# motordriver.net
KiCad netlist of a schematic drawn in Altium Designer
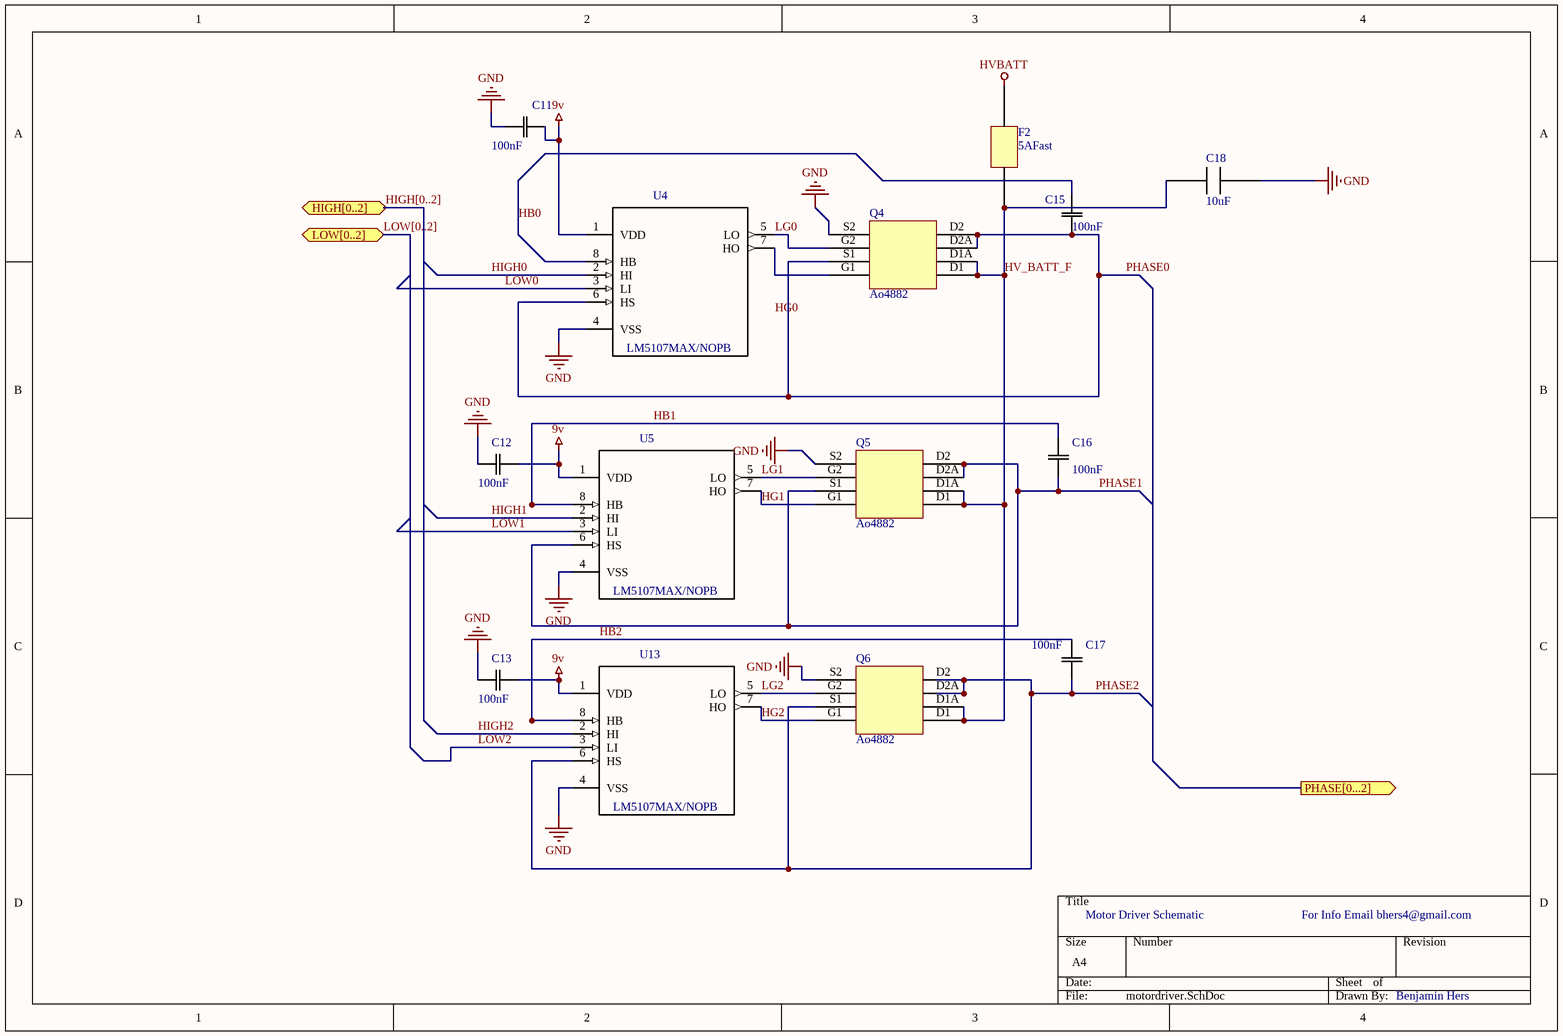
[diagram p0: motordriver.SchDoc]

(export (version "E")
  (design (tool "Eeschema 10.0.6"))
  (components
    (comp (ref "C11")
      (value "100nF")
      (footprint "CAPC2013X110N")
      (description "Capacitor; Ceramic; Cap; .100UF ; Tol+-10%; SMD; Vol-Rtg 50V; X7R, Tape/Reel")
      (fields (field (name "MP") "C0805C104K5RACTU") (field (name "MF") "Kemet"))
      (libsource (lib "100nF-C0805C104K5RACTU") (part "C0805C104K5RACTU"))
    )
    (comp (ref "C12")
      (value "100nF")
      (footprint "CAPC2013X110N")
      (description "Capacitor; Ceramic; Cap; .100UF ; Tol+-10%; SMD; Vol-Rtg 50V; X7R, Tape/Reel")
      (fields (field (name "MP") "C0805C104K5RACTU") (field (name "MF") "Kemet"))
      (libsource (lib "100nF-C0805C104K5RACTU") (part "C0805C104K5RACTU"))
    )
    (comp (ref "C13")
      (value "100nF")
      (footprint "CAPC2013X110N")
      (description "Capacitor; Ceramic; Cap; .100UF ; Tol+-10%; SMD; Vol-Rtg 50V; X7R, Tape/Reel")
      (fields (field (name "MP") "C0805C104K5RACTU") (field (name "MF") "Kemet"))
      (libsource (lib "100nF-C0805C104K5RACTU") (part "C0805C104K5RACTU"))
    )
    (comp (ref "C15")
      (value "100nF")
      (footprint "CAPC2013X110N")
      (description "Capacitor; Ceramic; Cap; .100UF ; Tol+-10%; SMD; Vol-Rtg 50V; X7R, Tape/Reel")
      (fields (field (name "MP") "C0805C104K5RACTU") (field (name "MF") "Kemet"))
      (libsource (lib "") (part "C0805C104K5RACTU_2"))
    )
    (comp (ref "C16")
      (value "100nF")
      (footprint "CAPC2013X110N")
      (description "Capacitor; Ceramic; Cap; .100UF ; Tol+-10%; SMD; Vol-Rtg 50V; X7R, Tape/Reel")
      (fields (field (name "MP") "C0805C104K5RACTU") (field (name "MF") "Kemet"))
      (libsource (lib "") (part "C0805C104K5RACTU_1"))
    )
    (comp (ref "C17")
      (value "100nF")
      (footprint "CAPC2013X110N")
      (description "Capacitor; Ceramic; Cap; .100UF ; Tol+-10%; SMD; Vol-Rtg 50V; X7R, Tape/Reel")
      (fields (field (name "MP") "C0805C104K5RACTU") (field (name "MF") "Kemet"))
      (libsource (lib "") (part "C0805C104K5RACTU_1"))
    )
    (comp (ref "C18")
      (value "10uF")
      (footprint "10uFCAPC3216X100N:CAPC3216X100N")
      (libsource (lib "altium-import") (part "root_0_Component_1_"))
    )
    (comp (ref "F2")
      (value "5AFast")
      (footprint "Fuse1206:1206")
      (libsource (lib "Fuse1206") (part "5AFast1206"))
    )
    (comp (ref "Q4")
      (value "Ao4882")
      (footprint "Ao4882:SOIC127P490X600X175-8N")
      (libsource (lib "Ao4882") (part "Ao4882"))
    )
    (comp (ref "Q5")
      (value "Ao4882")
      (footprint "Ao4882:SOIC127P490X600X175-8N")
      (libsource (lib "Ao4882") (part "Ao4882"))
    )
    (comp (ref "Q6")
      (value "Ao4882")
      (footprint "Ao4882:SOIC127P490X600X175-8N")
      (libsource (lib "Ao4882") (part "Ao4882"))
    )
    (comp (ref "U4")
      (value "LM5107MAX/NOPB")
      (footprint "LM5107MAX_NOPB:SOIC127P620X175-8N")
      (description "MOSFET DRVR 1.4A 2-OUT Hi/Lo Side Full Brdg/Half Brdg Non-Inv 8-Pin SOIC N T/R")
      (fields
        (field (name "DIGI-KEY_PART_NUMBER") "LM5107MAX/NOPBCT-ND")
        (field (name "MF") "Texas Instruments")
      )
      (libsource (lib "LM5107MAX_NOPB") (part "LM5107MAX/NOPB"))
    )
    (comp (ref "U5")
      (value "LM5107MAX/NOPB")
      (footprint "LM5107MAX_NOPB:SOIC127P620X175-8N")
      (description "MOSFET DRVR 1.4A 2-OUT Hi/Lo Side Full Brdg/Half Brdg Non-Inv 8-Pin SOIC N T/R")
      (fields
        (field (name "DIGI-KEY_PART_NUMBER") "LM5107MAX/NOPBCT-ND")
        (field (name "MF") "Texas Instruments")
      )
      (libsource (lib "LM5107MAX_NOPB") (part "LM5107MAX/NOPB"))
    )
    (comp (ref "U13")
      (value "LM5107MAX/NOPB")
      (footprint "LM5107MAX_NOPB:SOIC127P620X175-8N")
      (description "MOSFET DRVR 1.4A 2-OUT Hi/Lo Side Full Brdg/Half Brdg Non-Inv 8-Pin SOIC N T/R")
      (fields
        (field (name "DIGI-KEY_PART_NUMBER") "LM5107MAX/NOPBCT-ND")
        (field (name "MF") "Texas Instruments")
      )
      (libsource (lib "LM5107MAX_NOPB") (part "LM5107MAX/NOPB"))
    )
  )
  (nets
    (net (code "1") (name "/HB0") (class "Default")
      (node (ref "C15") (pin "2") (pinfunction "C2_2") (pintype "passive"))
      (node (ref "U4") (pin "8") (pinfunction "HB_8") (pintype "input"))
    )
    (net (code "2") (name "/HB1") (class "Default")
      (node (ref "C16") (pin "1") (pinfunction "C1_1") (pintype "passive"))
      (node (ref "U5") (pin "8") (pinfunction "HB_8") (pintype "input"))
    )
    (net (code "3") (name "/HB2") (class "Default")
      (node (ref "C17") (pin "1") (pinfunction "C1_1") (pintype "passive"))
      (node (ref "U13") (pin "8") (pinfunction "HB_8") (pintype "input"))
    )
    (net (code "5") (name "/HG1") (class "Default")
      (node (ref "Q5") (pin "G1") (pinfunction "4_G1") (pintype "passive"))
      (node (ref "U5") (pin "7") (pinfunction "HO_7") (pintype "output"))
    )
    (net (code "6") (name "/HG2") (class "Default")
      (node (ref "Q6") (pin "G1") (pinfunction "4_G1") (pintype "passive"))
      (node (ref "U13") (pin "7") (pinfunction "HO_7") (pintype "output"))
    )
    (net (code "7") (name "/HIGH0") (class "Default")
      (node (ref "U4") (pin "2") (pinfunction "HI_2") (pintype "input"))
    )
    (net (code "8") (name "/HIGH1") (class "Default")
      (node (ref "U5") (pin "2") (pinfunction "HI_2") (pintype "input"))
    )
    (net (code "9") (name "/HIGH2") (class "Default")
      (node (ref "U13") (pin "2") (pinfunction "HI_2") (pintype "input"))
    )
    (net (code "11") (name "/HV_BATT_F") (class "Default")
      (node (ref "F2") (pin "Fusein") (pinfunction "In_Fusein") (pintype "passive"))
      (node (ref "Q4") (pin "D1") (pinfunction "5_D1") (pintype "passive"))
      (node (ref "Q4") (pin "D1A") (pinfunction "6_D1A") (pintype "passive"))
      (node (ref "Q5") (pin "D1") (pinfunction "5_D1") (pintype "passive"))
      (node (ref "Q5") (pin "D1A") (pinfunction "6_D1A") (pintype "passive"))
      (node (ref "Q6") (pin "D1") (pinfunction "5_D1") (pintype "passive"))
      (node (ref "Q6") (pin "D1A") (pinfunction "6_D1A") (pintype "passive"))
    )
    (net (code "12") (name "/LG0") (class "Default")
      (node (ref "Q4") (pin "G2") (pinfunction "2_G2") (pintype "passive"))
      (node (ref "U4") (pin "5") (pinfunction "LO_5") (pintype "output"))
    )
    (net (code "13") (name "/LG1") (class "Default")
      (node (ref "Q5") (pin "G2") (pinfunction "2_G2") (pintype "passive"))
      (node (ref "U5") (pin "5") (pinfunction "LO_5") (pintype "output"))
    )
    (net (code "14") (name "/LG2") (class "Default")
      (node (ref "Q6") (pin "G2") (pinfunction "2_G2") (pintype "passive"))
      (node (ref "U13") (pin "5") (pinfunction "LO_5") (pintype "output"))
    )
    (net (code "15") (name "/LOW0") (class "Default")
      (node (ref "U4") (pin "3") (pinfunction "LI_3") (pintype "input"))
    )
    (net (code "16") (name "/LOW1") (class "Default")
      (node (ref "U5") (pin "3") (pinfunction "LI_3") (pintype "input"))
    )
    (net (code "17") (name "/LOW2") (class "Default")
      (node (ref "U13") (pin "3") (pinfunction "LI_3") (pintype "input"))
    )
    (net (code "19") (name "/PHASE0") (class "Default")
      (node (ref "C15") (pin "1") (pinfunction "C1_1") (pintype "passive"))
      (node (ref "Q4") (pin "D2") (pinfunction "8_D2") (pintype "passive"))
      (node (ref "Q4") (pin "D2A") (pinfunction "7_D2A") (pintype "passive"))
      (node (ref "Q4") (pin "S1") (pinfunction "3_S1") (pintype "passive"))
      (node (ref "U4") (pin "6") (pinfunction "HS_6") (pintype "input"))
    )
    (net (code "20") (name "/PHASE1") (class "Default")
      (node (ref "C16") (pin "2") (pinfunction "C2_2") (pintype "passive"))
      (node (ref "Q5") (pin "D2") (pinfunction "8_D2") (pintype "passive"))
      (node (ref "Q5") (pin "D2A") (pinfunction "7_D2A") (pintype "passive"))
      (node (ref "Q5") (pin "S1") (pinfunction "3_S1") (pintype "passive"))
      (node (ref "U5") (pin "6") (pinfunction "HS_6") (pintype "input"))
    )
    (net (code "21") (name "/PHASE2") (class "Default")
      (node (ref "C17") (pin "2") (pinfunction "C2_2") (pintype "passive"))
      (node (ref "Q6") (pin "D2") (pinfunction "8_D2") (pintype "passive"))
      (node (ref "Q6") (pin "D2A") (pinfunction "7_D2A") (pintype "passive"))
      (node (ref "Q6") (pin "S1") (pinfunction "3_S1") (pintype "passive"))
      (node (ref "U13") (pin "6") (pinfunction "HS_6") (pintype "input"))
    )
    (net (code "23") (name "9v") (class "Default")
      (node (ref "C11") (pin "1") (pinfunction "C1_1") (pintype "passive"))
      (node (ref "C12") (pin "2") (pinfunction "C2_2") (pintype "passive"))
      (node (ref "C13") (pin "2") (pinfunction "C2_2") (pintype "passive"))
      (node (ref "U13") (pin "1") (pinfunction "VDD_1") (pintype "power_in"))
      (node (ref "U4") (pin "1") (pinfunction "VDD_1") (pintype "power_in"))
      (node (ref "U5") (pin "1") (pinfunction "VDD_1") (pintype "power_in"))
    )
    (net (code "24") (name "GND") (class "Default")
      (node (ref "C11") (pin "2") (pinfunction "C2_2") (pintype "passive"))
      (node (ref "C12") (pin "1") (pinfunction "C1_1") (pintype "passive"))
      (node (ref "C13") (pin "1") (pinfunction "C1_1") (pintype "passive"))
      (node (ref "Q4") (pin "S2") (pinfunction "1_S2") (pintype "passive"))
      (node (ref "Q5") (pin "S2") (pinfunction "1_S2") (pintype "passive"))
      (node (ref "Q6") (pin "S2") (pinfunction "1_S2") (pintype "passive"))
      (node (ref "U13") (pin "4") (pinfunction "VSS_4") (pintype "power_in"))
      (node (ref "U4") (pin "4") (pinfunction "VSS_4") (pintype "power_in"))
      (node (ref "U5") (pin "4") (pinfunction "VSS_4") (pintype "power_in"))
    )
    (net (code "25") (name "HVBATT") (class "Default")
      (node (ref "F2") (pin "Fuseout") (pinfunction "Out_Fuseout") (pintype "passive"))
    )
    (net (code "26") (name "Net-(Q4-4)") (class "Default")
      (node (ref "Q4") (pin "G1") (pinfunction "4_G1") (pintype "passive"))
      (node (ref "U4") (pin "7") (pinfunction "HO_7") (pintype "output"))
    )
    (net (code "27") (name "unconnected-(C18-PadIn)") (class "Default")
      (node (ref "C18") (pin "In") (pinfunction "In_In") (pintype "passive"))
    )
    (net (code "28") (name "unconnected-(C18-PadOut)") (class "Default")
      (node (ref "C18") (pin "Out") (pinfunction "Out_Out") (pintype "passive"))
    )
  )
)
